# SWD_Touch_USB.net
KiCad netlist of a schematic drawn in Altium Designer
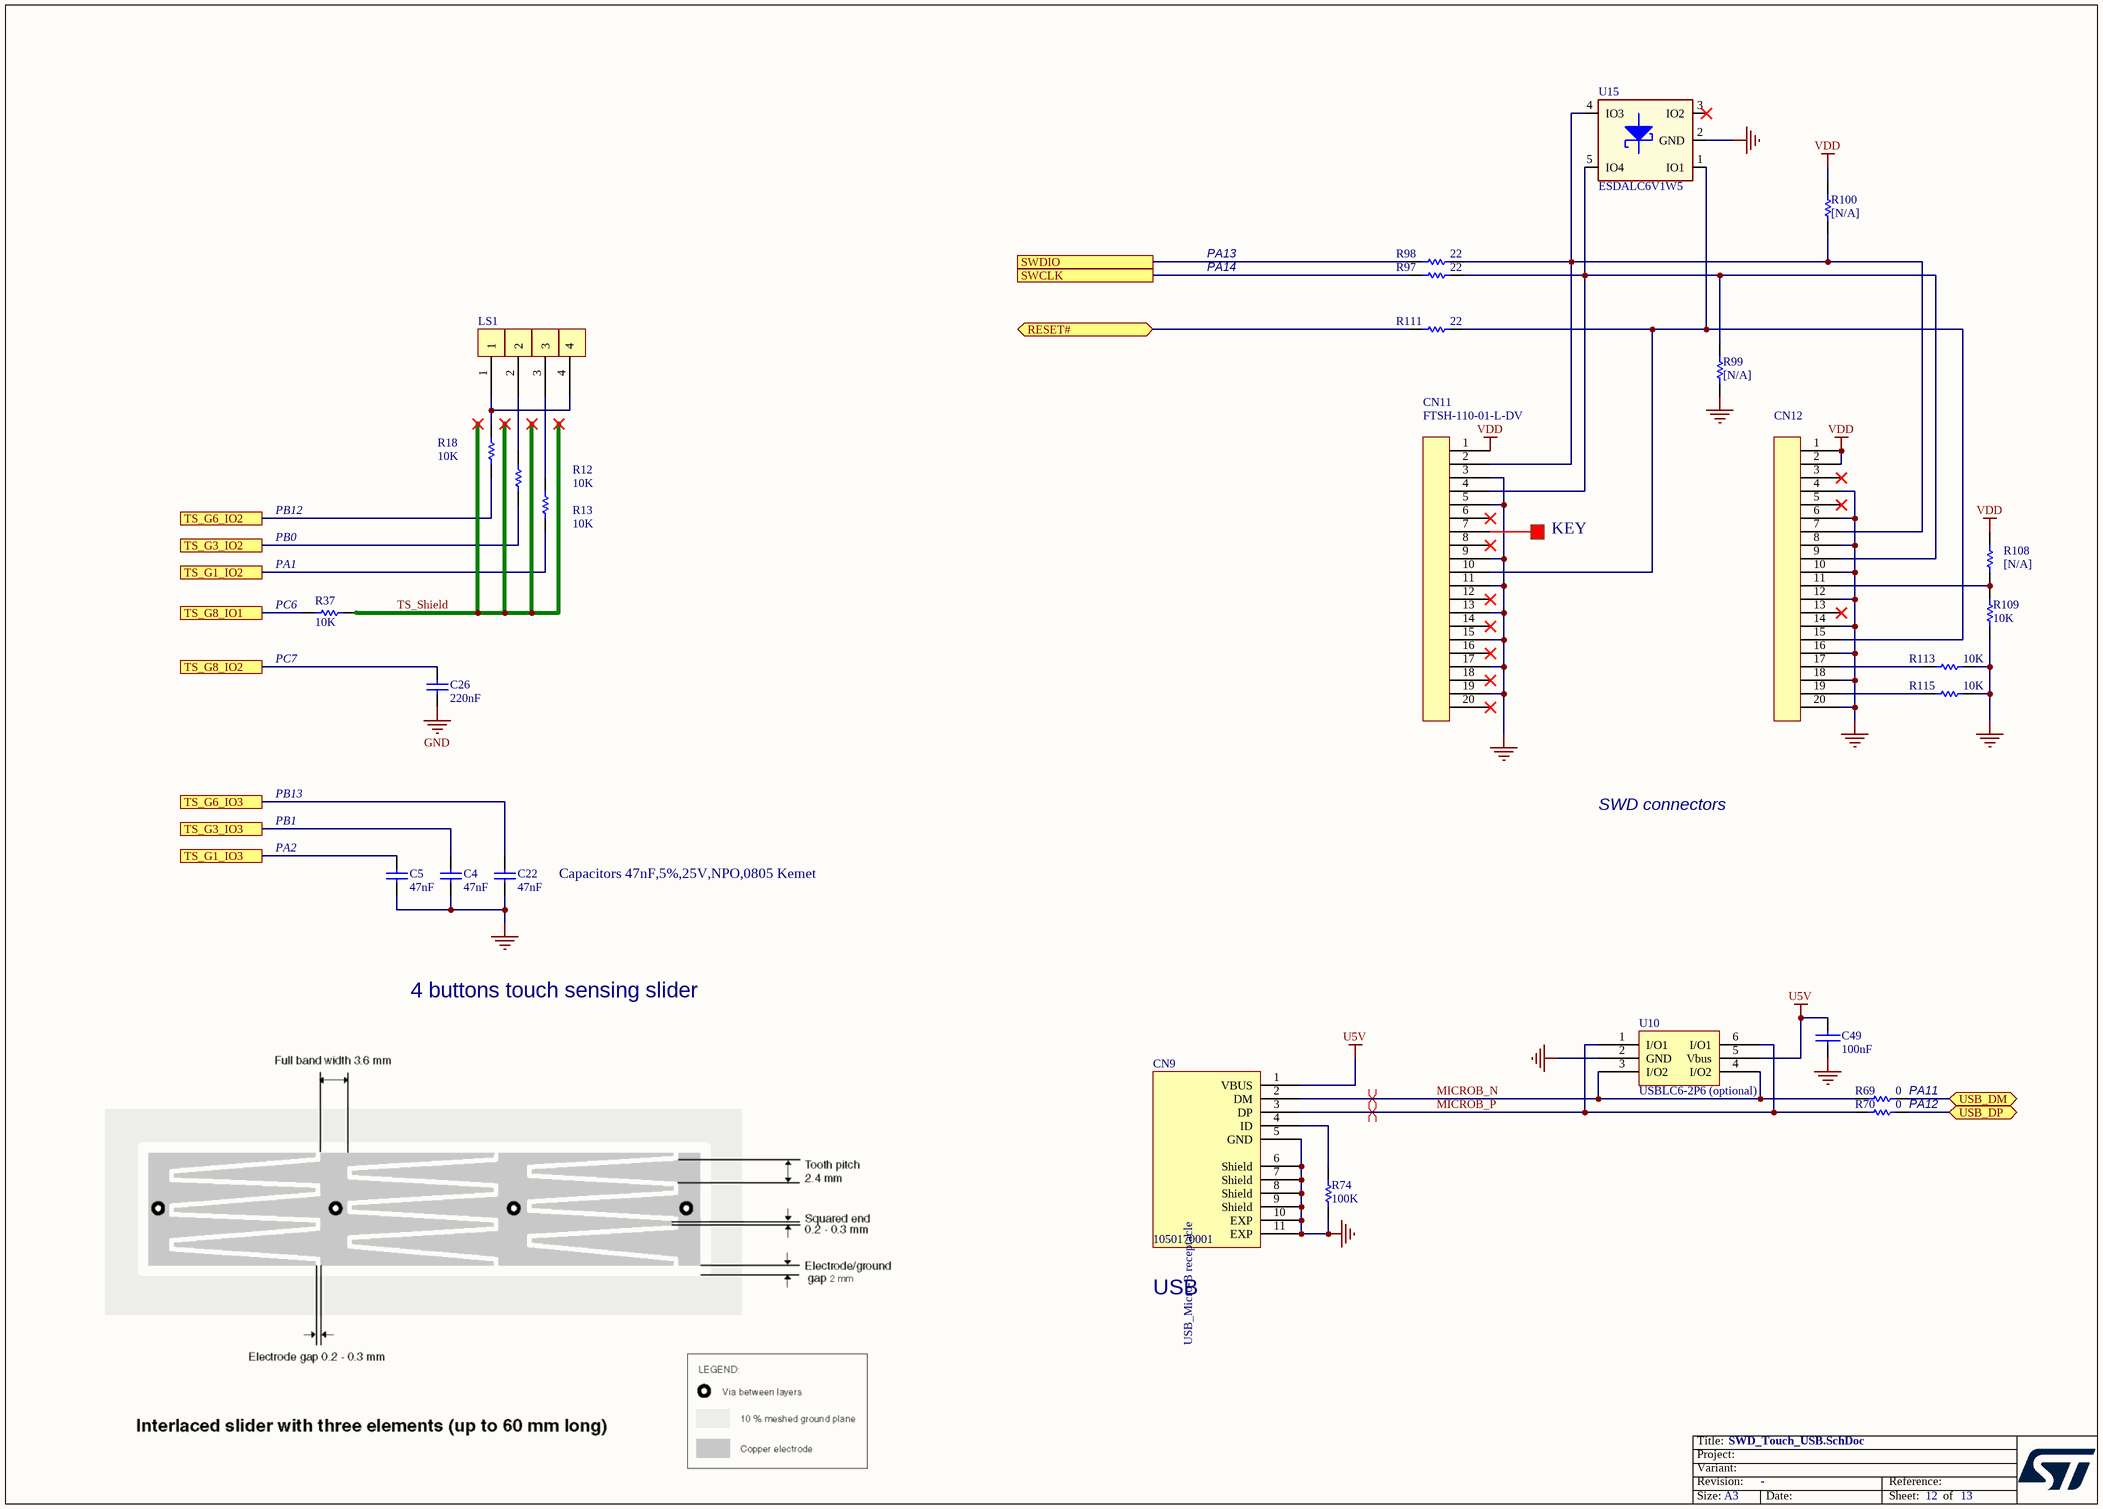
[diagram p0: SWD_Touch_USB.SchDoc]

(export (version "E")
  (design (tool "Eeschema 10.0.6"))
  (components
    (comp (ref "C4")
      (value "47nF")
      (footprint "0805C")
      (description "Capacitor 47nF,5%,25V,NPO,0805 Kemet")
      (libsource (lib "MCD_TOOLS") (part "Cap_47nF_NPO_5%"))
    )
    (comp (ref "C5")
      (value "47nF")
      (footprint "0805C")
      (description "Capacitor 47nF,5%,25V,NPO,0805 Kemet")
      (libsource (lib "MCD_TOOLS") (part "Cap_47nF_NPO_5%"))
    )
    (comp (ref "C22")
      (value "47nF")
      (footprint "0805C")
      (description "Capacitor 47nF,5%,25V,NPO,0805 Kemet")
      (libsource (lib "MCD_TOOLS") (part "Cap_47nF_NPO_5%"))
    )
    (comp (ref "C26")
      (value "220nF")
      (footprint "0603C")
      (description "Capacitor")
      (fields (field (name "PUBLISHER") "Altium Limited"))
      (libsource (lib "Miscellaneous Devices") (part "Cap"))
    )
    (comp (ref "C49")
      (value "100nF")
      (footprint "0402C")
      (description "Capacitor")
      (libsource (lib "*") (part "CAP"))
    )
    (comp (ref "CN9")
      (value "1050170001")
      (footprint "MICRO_USB_B_105017")
      (libsource (lib "Smartphone_accessory") (part "1050170001"))
    )
    (comp (ref "CN11")
      (value "FTSH-110-01-L-DV")
      (footprint "FTSH-110-01-L-DV")
      (libsource (lib "*") (part "20PIN1"))
    )
    (comp (ref "CN12") (value "JTAG") (footprint "IDC20S") (libsource (lib "*") (part "20PIN1")))
    (comp (ref "LS1")
      (value "LS4")
      (footprint "LINEAR_SENSOR3_ELECTRODES")
      (libsource (lib "Almos") (part "LS4"))
    )
    (comp (ref "R12")
      (value "10K")
      (footprint "0603R")
      (description "Resistor")
      (fields (field (name "PUBLISHER") "Altium Limited"))
      (libsource (lib "Miscellaneous Devices") (part "res1"))
    )
    (comp (ref "R13")
      (value "10K")
      (footprint "0603R")
      (description "Resistor")
      (fields (field (name "PUBLISHER") "Altium Limited"))
      (libsource (lib "Miscellaneous Devices") (part "res1"))
    )
    (comp (ref "R18")
      (value "10K")
      (footprint "0603R")
      (description "Resistor")
      (fields (field (name "PUBLISHER") "Altium Limited"))
      (libsource (lib "Miscellaneous Devices") (part "res1"))
    )
    (comp (ref "R37")
      (value "10K")
      (footprint "0603R")
      (description "Resistor")
      (fields (field (name "PUBLISHER") "Altium Limited"))
      (libsource (lib "Miscellaneous Devices") (part "res1"))
    )
    (comp (ref "R69")
      (value "0")
      (footprint "0603R")
      (description "Resistor")
      (fields (field (name "PUBLISHER") "Altium Limited"))
      (libsource (lib "Miscellaneous Devices") (part "Res1"))
    )
    (comp (ref "R70")
      (value "0")
      (footprint "0603R")
      (description "Resistor")
      (fields (field (name "PUBLISHER") "Altium Limited"))
      (libsource (lib "Miscellaneous Devices") (part "Res1"))
    )
    (comp (ref "R74")
      (value "100K")
      (footprint "0603R")
      (description "Resistor")
      (fields (field (name "PUBLISHER") "Altium Limited"))
      (libsource (lib "Miscellaneous Devices") (part "Res1"))
    )
    (comp (ref "R97")
      (value "22")
      (footprint "0402R")
      (description "Resistor")
      (fields (field (name "PUBLISHER") "Altium Limited"))
      (libsource (lib "Miscellaneous Devices") (part "Res1"))
    )
    (comp (ref "R98")
      (value "22")
      (footprint "0402R")
      (description "Resistor")
      (fields (field (name "PUBLISHER") "Altium Limited"))
      (libsource (lib "Miscellaneous Devices") (part "Res1"))
    )
    (comp (ref "R99")
      (value "[N/A]")
      (footprint "0603R")
      (description "Resistor")
      (fields (field (name "PUBLISHER") "Altium Limited"))
      (libsource (lib "Miscellaneous Devices") (part "Res1"))
    )
    (comp (ref "R100")
      (value "[N/A]")
      (footprint "0603R")
      (description "Resistor")
      (fields (field (name "PUBLISHER") "Altium Limited"))
      (libsource (lib "Miscellaneous Devices") (part "Res1"))
    )
    (comp (ref "R108")
      (value "[N/A]")
      (footprint "0603R")
      (description "Resistor")
      (fields (field (name "PUBLISHER") "Altium Limited"))
      (libsource (lib "Miscellaneous Devices") (part "Res1"))
    )
    (comp (ref "R109")
      (value "10K")
      (footprint "0402R")
      (description "Resistor")
      (fields (field (name "PUBLISHER") "Altium Limited"))
      (libsource (lib "Miscellaneous Devices") (part "Res1"))
    )
    (comp (ref "R111")
      (value "22")
      (footprint "0402R")
      (description "Resistor")
      (fields (field (name "PUBLISHER") "Altium Limited"))
      (libsource (lib "Miscellaneous Devices") (part "Res1"))
    )
    (comp (ref "R113")
      (value "10K")
      (footprint "0402R")
      (description "Resistor")
      (fields (field (name "PUBLISHER") "Altium Limited"))
      (libsource (lib "Miscellaneous Devices") (part "Res1"))
    )
    (comp (ref "R115")
      (value "10K")
      (footprint "0402R")
      (description "Resistor")
      (fields (field (name "PUBLISHER") "Altium Limited"))
      (libsource (lib "Miscellaneous Devices") (part "Res1"))
    )
    (comp (ref "U10")
      (value "USBLC6-2P6 (optional)")
      (footprint "SOT-563")
      (libsource (lib "STR910_SCHLIB") (part "USBLC6-2"))
    )
    (comp (ref "U15")
      (value "ESDALC6V1W5")
      (footprint "SOT-353")
      (description "Dual Transil array for ESD protection")
      (libsource (lib "orcaeval_3") (part "ESDALC6V1W5"))
    )
  )
  (nets
    (net (code "1") (name "/MICROB_N") (class "Default")
      (node (ref "CN9") (pin "2") (pinfunction "DM_2") (pintype "passive"))
      (node (ref "R69") (pin "2") (pinfunction "2_2") (pintype "passive"))
      (node (ref "U10") (pin "3") (pinfunction "I/O2_3") (pintype "passive"))
      (node (ref "U10") (pin "4") (pinfunction "I/O2_4") (pintype "passive"))
    )
    (net (code "2") (name "/MICROB_P") (class "Default")
      (node (ref "CN9") (pin "3") (pinfunction "DP_3") (pintype "passive"))
      (node (ref "R70") (pin "2") (pinfunction "2_2") (pintype "passive"))
      (node (ref "U10") (pin "1") (pinfunction "I/O1_1") (pintype "passive"))
      (node (ref "U10") (pin "6") (pinfunction "I/O1_6") (pintype "passive"))
    )
    (net (code "3") (name "/RESET#") (class "Default")
      (node (ref "R111") (pin "2") (pinfunction "2_2") (pintype "passive"))
    )
    (net (code "4") (name "/SWCLK") (class "Default")
      (node (ref "R97") (pin "2") (pinfunction "2_2") (pintype "passive"))
    )
    (net (code "5") (name "/SWDIO") (class "Default")
      (node (ref "R98") (pin "2") (pinfunction "2_2") (pintype "passive"))
    )
    (net (code "6") (name "/TS_G1_IO2") (class "Default")
      (node (ref "R13") (pin "1") (pinfunction "1_1") (pintype "passive"))
    )
    (net (code "7") (name "/TS_G1_IO3") (class "Default")
      (node (ref "C5") (pin "2") (pinfunction "2_2") (pintype "passive"))
    )
    (net (code "8") (name "/TS_G3_IO2") (class "Default")
      (node (ref "R12") (pin "1") (pinfunction "1_1") (pintype "passive"))
    )
    (net (code "9") (name "/TS_G3_IO3") (class "Default")
      (node (ref "C4") (pin "2") (pinfunction "2_2") (pintype "passive"))
    )
    (net (code "10") (name "/TS_G6_IO2") (class "Default")
      (node (ref "R18") (pin "1") (pinfunction "1_1") (pintype "passive"))
    )
    (net (code "11") (name "/TS_G6_IO3") (class "Default")
      (node (ref "C22") (pin "2") (pinfunction "2_2") (pintype "passive"))
    )
    (net (code "12") (name "/TS_G8_IO1") (class "Default")
      (node (ref "R37") (pin "2") (pinfunction "2_2") (pintype "passive"))
    )
    (net (code "13") (name "/TS_G8_IO2") (class "Default")
      (node (ref "C26") (pin "2") (pinfunction "2_2") (pintype "passive"))
    )
    (net (code "14") (name "/TS_Shield") (class "Default")
      (node (ref "R37") (pin "1") (pinfunction "1_1") (pintype "passive+no_connect"))
    )
    (net (code "15") (name "/USB_DM") (class "Default")
      (node (ref "R69") (pin "1") (pinfunction "1_1") (pintype "passive"))
    )
    (net (code "16") (name "/USB_DP") (class "Default")
      (node (ref "R70") (pin "1") (pinfunction "1_1") (pintype "passive"))
    )
    (net (code "17") (name "GND") (class "Default")
      (node (ref "C22") (pin "1") (pinfunction "1_1") (pintype "passive"))
      (node (ref "C26") (pin "1") (pinfunction "1_1") (pintype "passive"))
      (node (ref "C4") (pin "1") (pinfunction "1_1") (pintype "passive"))
      (node (ref "C49") (pin "2") (pinfunction "2_2") (pintype "passive"))
      (node (ref "C5") (pin "1") (pinfunction "1_1") (pintype "passive"))
      (node (ref "CN11") (pin "11") (pintype "passive"))
      (node (ref "CN11") (pin "13") (pintype "passive"))
      (node (ref "CN11") (pin "15") (pintype "passive"))
      (node (ref "CN11") (pin "17") (pintype "passive"))
      (node (ref "CN11") (pin "19") (pintype "passive"))
      (node (ref "CN11") (pin "3") (pintype "passive"))
      (node (ref "CN11") (pin "5") (pintype "passive"))
      (node (ref "CN11") (pin "9") (pintype "passive"))
      (node (ref "CN12") (pin "10") (pintype "passive"))
      (node (ref "CN12") (pin "12") (pintype "passive"))
      (node (ref "CN12") (pin "14") (pintype "passive"))
      (node (ref "CN12") (pin "16") (pintype "passive"))
      (node (ref "CN12") (pin "18") (pintype "passive"))
      (node (ref "CN12") (pin "20") (pintype "passive"))
      (node (ref "CN12") (pin "4") (pintype "passive"))
      (node (ref "CN12") (pin "6") (pintype "passive"))
      (node (ref "CN12") (pin "8") (pintype "passive"))
      (node (ref "CN9") (pin "10") (pinfunction "EXP_10") (pintype "passive"))
      (node (ref "CN9") (pin "11") (pinfunction "EXP_11") (pintype "passive"))
      (node (ref "CN9") (pin "5") (pinfunction "GND_5") (pintype "passive"))
      (node (ref "CN9") (pin "6") (pinfunction "Shield_6") (pintype "passive"))
      (node (ref "CN9") (pin "7") (pinfunction "Shield_7") (pintype "passive"))
      (node (ref "CN9") (pin "8") (pinfunction "Shield_8") (pintype "passive"))
      (node (ref "CN9") (pin "9") (pinfunction "Shield_9") (pintype "passive"))
      (node (ref "R109") (pin "1") (pinfunction "1_1") (pintype "passive"))
      (node (ref "R113") (pin "1") (pinfunction "1_1") (pintype "passive"))
      (node (ref "R115") (pin "1") (pinfunction "1_1") (pintype "passive"))
      (node (ref "R74") (pin "1") (pinfunction "1_1") (pintype "passive"))
      (node (ref "R99") (pin "1") (pinfunction "1_1") (pintype "passive"))
      (node (ref "U10") (pin "2") (pinfunction "GND_2") (pintype "passive"))
      (node (ref "U15") (pin "2") (pinfunction "GND_2") (pintype "passive"))
    )
    (net (code "18") (name "Net-(CN9-ID)") (class "Default")
      (node (ref "CN9") (pin "4") (pinfunction "ID_4") (pintype "passive"))
      (node (ref "R74") (pin "2") (pinfunction "2_2") (pintype "passive"))
    )
    (net (code "19") (name "Net-(CN12-Pad11)") (class "Default")
      (node (ref "CN12") (pin "11") (pintype "passive"))
      (node (ref "R108") (pin "1") (pinfunction "1_1") (pintype "passive"))
      (node (ref "R109") (pin "2") (pinfunction "2_2") (pintype "passive"))
    )
    (net (code "20") (name "Net-(CN12-Pad17)") (class "Default")
      (node (ref "CN12") (pin "17") (pintype "passive"))
      (node (ref "R113") (pin "2") (pinfunction "2_2") (pintype "passive"))
    )
    (net (code "21") (name "Net-(CN12-Pad19)") (class "Default")
      (node (ref "CN12") (pin "19") (pintype "passive"))
      (node (ref "R115") (pin "2") (pinfunction "2_2") (pintype "passive"))
    )
    (net (code "22") (name "Net-(LS1-Pad1)") (class "Default")
      (node (ref "LS1") (pin "1") (pinfunction "1_1") (pintype "passive"))
      (node (ref "LS1") (pin "4") (pinfunction "4_4") (pintype "passive"))
      (node (ref "R18") (pin "2") (pinfunction "2_2") (pintype "passive"))
    )
    (net (code "23") (name "Net-(LS1-Pad2)") (class "Default")
      (node (ref "LS1") (pin "2") (pinfunction "2_2") (pintype "passive"))
      (node (ref "R12") (pin "2") (pinfunction "2_2") (pintype "passive"))
    )
    (net (code "24") (name "Net-(LS1-Pad3)") (class "Default")
      (node (ref "LS1") (pin "3") (pinfunction "3_3") (pintype "passive"))
      (node (ref "R13") (pin "2") (pinfunction "2_2") (pintype "passive"))
    )
    (net (code "25") (name "Net-(U15-IO1)") (class "Default")
      (node (ref "CN11") (pin "10") (pintype "passive"))
      (node (ref "CN12") (pin "15") (pintype "passive"))
      (node (ref "R111") (pin "1") (pinfunction "1_1") (pintype "passive"))
      (node (ref "U15") (pin "1") (pinfunction "IO1_1") (pintype "passive"))
    )
    (net (code "26") (name "Net-(U15-IO3)") (class "Default")
      (node (ref "CN11") (pin "2") (pintype "passive"))
      (node (ref "CN12") (pin "7") (pintype "passive"))
      (node (ref "R100") (pin "1") (pinfunction "1_1") (pintype "passive"))
      (node (ref "R98") (pin "1") (pinfunction "1_1") (pintype "passive"))
      (node (ref "U15") (pin "4") (pinfunction "IO3_4") (pintype "passive"))
    )
    (net (code "27") (name "Net-(U15-IO4)") (class "Default")
      (node (ref "CN11") (pin "4") (pintype "passive"))
      (node (ref "CN12") (pin "9") (pintype "passive"))
      (node (ref "R97") (pin "1") (pinfunction "1_1") (pintype "passive"))
      (node (ref "R99") (pin "2") (pinfunction "2_2") (pintype "passive"))
      (node (ref "U15") (pin "5") (pinfunction "IO4_5") (pintype "passive"))
    )
    (net (code "28") (name "U5V") (class "Default")
      (node (ref "C49") (pin "1") (pinfunction "1_1") (pintype "passive"))
      (node (ref "CN9") (pin "1") (pinfunction "VBUS_1") (pintype "passive"))
      (node (ref "U10") (pin "5") (pinfunction "Vbus_5") (pintype "passive"))
    )
    (net (code "29") (name "VDD") (class "Default")
      (node (ref "CN11") (pin "1") (pintype "passive"))
      (node (ref "CN12") (pin "1") (pintype "passive"))
      (node (ref "CN12") (pin "2") (pintype "passive"))
      (node (ref "R100") (pin "2") (pinfunction "2_2") (pintype "passive"))
      (node (ref "R108") (pin "2") (pinfunction "2_2") (pintype "passive"))
    )
    (net (code "30") (name "unconnected-(CN11-Pad6)") (class "Default")
      (node (ref "CN11") (pin "6") (pintype "passive+no_connect"))
    )
    (net (code "31") (name "unconnected-(CN11-Pad7)") (class "Default")
      (node (ref "CN11") (pin "7") (pintype "passive"))
    )
    (net (code "32") (name "unconnected-(CN11-Pad8)") (class "Default")
      (node (ref "CN11") (pin "8") (pintype "passive+no_connect"))
    )
    (net (code "33") (name "unconnected-(CN11-Pad12)") (class "Default")
      (node (ref "CN11") (pin "12") (pintype "passive+no_connect"))
    )
    (net (code "34") (name "unconnected-(CN11-Pad14)") (class "Default")
      (node (ref "CN11") (pin "14") (pintype "passive+no_connect"))
    )
    (net (code "35") (name "unconnected-(CN11-Pad16)") (class "Default")
      (node (ref "CN11") (pin "16") (pintype "passive+no_connect"))
    )
    (net (code "36") (name "unconnected-(CN11-Pad18)") (class "Default")
      (node (ref "CN11") (pin "18") (pintype "passive+no_connect"))
    )
    (net (code "37") (name "unconnected-(CN11-Pad20)") (class "Default")
      (node (ref "CN11") (pin "20") (pintype "passive+no_connect"))
    )
    (net (code "38") (name "unconnected-(CN12-Pad3)") (class "Default")
      (node (ref "CN12") (pin "3") (pintype "passive+no_connect"))
    )
    (net (code "39") (name "unconnected-(CN12-Pad5)") (class "Default")
      (node (ref "CN12") (pin "5") (pintype "passive+no_connect"))
    )
    (net (code "40") (name "unconnected-(CN12-Pad13)") (class "Default")
      (node (ref "CN12") (pin "13") (pintype "passive+no_connect"))
    )
    (net (code "41") (name "unconnected-(U15-IO2-Pad3)") (class "Default")
      (node (ref "U15") (pin "3") (pinfunction "IO2_3") (pintype "passive+no_connect"))
    )
  )
)
